# thick.net
KiCad netlist of a schematic drawn in EAGLE
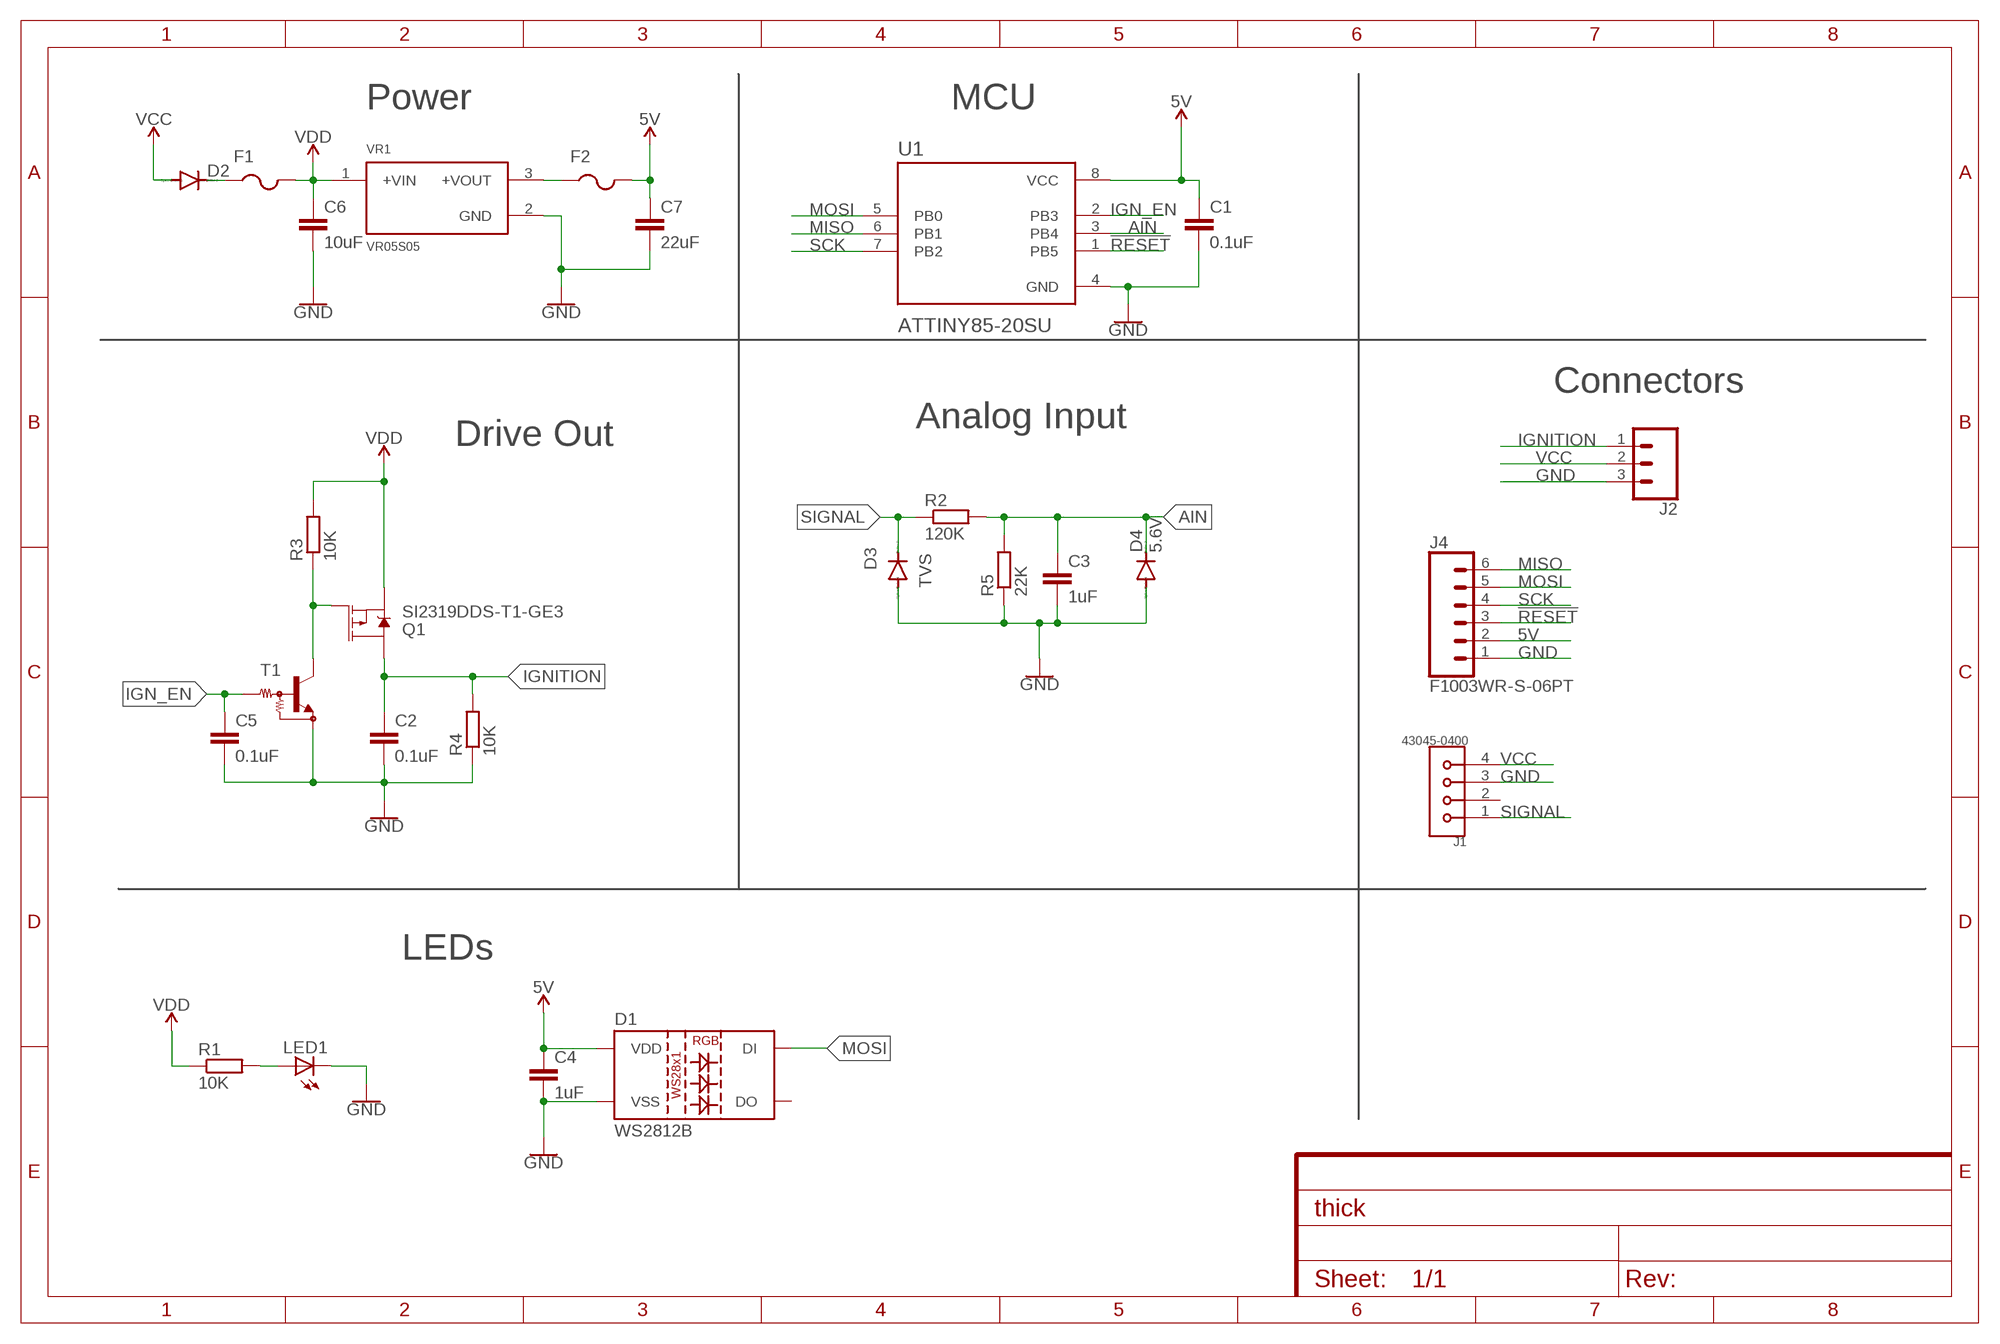
[diagram p0: schematic, sheet 1]

(export (version "E")
  (design (tool "Eeschema 10.0.6"))
  (components
    (comp (ref "C1")
      (value "0.1uF")
      (footprint "eagle-import:C0603")
      (libsource (lib "eagle-import") (part "C-EUC0603"))
    )
    (comp (ref "C2")
      (value "0.1uF")
      (footprint "eagle-import:C0603")
      (libsource (lib "eagle-import") (part "C-EUC0603"))
    )
    (comp (ref "C3")
      (value "1uF")
      (footprint "eagle-import:C0603")
      (libsource (lib "eagle-import") (part "C-EUC0603"))
    )
    (comp (ref "C4")
      (value "1uF")
      (footprint "eagle-import:C0603")
      (libsource (lib "eagle-import") (part "C-EUC0603"))
    )
    (comp (ref "C5")
      (value "0.1uF")
      (footprint "eagle-import:C0603")
      (libsource (lib "eagle-import") (part "C-EUC0603"))
    )
    (comp (ref "C6")
      (value "10uF")
      (footprint "eagle-import:C1206")
      (libsource (lib "eagle-import") (part "C-EUC1206"))
    )
    (comp (ref "C7")
      (value "22uF")
      (footprint "eagle-import:C0603")
      (libsource (lib "eagle-import") (part "C-EUC0603"))
    )
    (comp (ref "D1")
      (value "WS2812B")
      (footprint "eagle-import:WS2812B")
      (libsource (lib "eagle-import") (part "WS2812B"))
    )
    (comp (ref "D2")
      (value "DIODE-MINIMELF")
      (footprint "eagle-import:MINIMELF")
      (libsource (lib "eagle-import") (part "DIODE-MINIMELF"))
    )
    (comp (ref "D3")
      (value "TVS")
      (footprint "eagle-import:DO214AC")
      (libsource (lib "eagle-import") (part "DIODE-DO214AC"))
    )
    (comp (ref "D4")
      (value "5.6V")
      (footprint "eagle-import:MINIMELF")
      (libsource (lib "eagle-import") (part "DIODE-MINIMELF"))
    )
    (comp (ref "F1")
      (value "PTCFUSE-1206")
      (footprint "eagle-import:R1206")
      (libsource (lib "eagle-import") (part "PTCFUSE-1206"))
    )
    (comp (ref "F2")
      (value "PTCFUSE-1206")
      (footprint "eagle-import:R1206")
      (libsource (lib "eagle-import") (part "PTCFUSE-1206"))
    )
    (comp (ref "J1")
      (value "43045-0400")
      (footprint "eagle-import:MOLEX_43045-0400")
      (fields (field (name "MF") "Molex"))
      (libsource (lib "eagle-import") (part "43045-0400"))
    )
    (comp (ref "J2")
      (value "CONN_03LONGPADS")
      (footprint "eagle-import:1X03_LONGPADS")
      (libsource (lib "eagle-import") (part "CONN_03LONGPADS"))
    )
    (comp (ref "J4")
      (value "F1003WR-S-06PT")
      (footprint "eagle-import:1X06-1MM")
      (libsource (lib "eagle-import") (part "F1003WR-S-06PT"))
    )
    (comp (ref "LED1")
      (value "LEDCHIPLED_0805")
      (footprint "eagle-import:CHIPLED_0805")
      (libsource (lib "eagle-import") (part "LEDCHIPLED_0805"))
    )
    (comp (ref "Q1")
      (value "SI2319DDS-T1-GE3")
      (footprint "eagle-import:SOT23-3")
      (libsource (lib "eagle-import") (part "MOSFET_PCH-DMG2307L"))
    )
    (comp (ref "R1")
      (value "10K")
      (footprint "eagle-import:R0603")
      (libsource (lib "eagle-import") (part "R-EU_R0603"))
    )
    (comp (ref "R2")
      (value "120K")
      (footprint "eagle-import:R0603")
      (libsource (lib "eagle-import") (part "R-EU_R0603"))
    )
    (comp (ref "R3")
      (value "10K")
      (footprint "eagle-import:R0603")
      (libsource (lib "eagle-import") (part "R-EU_R0603"))
    )
    (comp (ref "R4")
      (value "10K")
      (footprint "eagle-import:R0603")
      (libsource (lib "eagle-import") (part "R-EU_R0603"))
    )
    (comp (ref "R5")
      (value "22K")
      (footprint "eagle-import:R0603")
      (libsource (lib "eagle-import") (part "R-EU_R0603"))
    )
    (comp (ref "T1")
      (value "MUN2213T1-NPN_DRIVER-SC59-BEC")
      (footprint "eagle-import:SC59-BEC")
      (libsource (lib "eagle-import") (part "-NPN_DRIVER-SC59-BECMUN2213T1"))
    )
    (comp (ref "U1")
      (value "ATTINY85-20SU")
      (footprint "eagle-import:SOIC127P798X216-8N")
      (fields (field (name "MF") "Microchip Technology"))
      (libsource (lib "eagle-import") (part "ATTINY85-20SU"))
    )
    (comp (ref "VR1")
      (value "VR05S05")
      (footprint "eagle-import:CONV_TSR_1-24150")
      (fields (field (name "MF") "Traco Power") (field (name "MP") "TSR 1-24150"))
      (libsource (lib "eagle-import") (part "TSR_1-24150"))
    )
  )
  (nets
    (net (code "1") (name "/MISO") (class "Default")
      (node (ref "J4") (pin "6") (pinfunction "6_6") (pintype "passive"))
      (node (ref "U1") (pin "6") (pinfunction "PB1_6") (pintype "bidirectional"))
    )
    (net (code "2") (name "/SCK") (class "Default")
      (node (ref "J4") (pin "4") (pinfunction "4_4") (pintype "passive"))
      (node (ref "U1") (pin "7") (pinfunction "PB2_7") (pintype "bidirectional"))
    )
    (net (code "3") (name "/~{RESET}") (class "Default")
      (node (ref "J4") (pin "3") (pinfunction "3_3") (pintype "passive"))
      (node (ref "U1") (pin "1") (pinfunction "PB5_1") (pintype "bidirectional"))
    )
    (net (code "4") (name "5V") (class "Default")
      (node (ref "C1") (pin "1") (pinfunction "1_1") (pintype "passive"))
      (node (ref "C4") (pin "1") (pinfunction "1_1") (pintype "passive"))
      (node (ref "C7") (pin "1") (pinfunction "1_1") (pintype "passive"))
      (node (ref "D1") (pin "1") (pinfunction "VDD_1") (pintype "bidirectional"))
      (node (ref "F2") (pin "2") (pinfunction "2_2") (pintype "passive"))
      (node (ref "J4") (pin "2") (pinfunction "2_2") (pintype "passive"))
      (node (ref "U1") (pin "8") (pinfunction "VCC_8") (pintype "power_in"))
    )
    (net (code "5") (name "AIN") (class "Default")
      (node (ref "C3") (pin "1") (pinfunction "1_1") (pintype "passive"))
      (node (ref "D4") (pin "C") (pinfunction "C_C") (pintype "passive"))
      (node (ref "R2") (pin "2") (pinfunction "2_2") (pintype "passive"))
      (node (ref "R5") (pin "2") (pinfunction "2_2") (pintype "passive"))
      (node (ref "U1") (pin "3") (pinfunction "PB4_3") (pintype "bidirectional"))
    )
    (net (code "6") (name "GND") (class "Default")
      (node (ref "C1") (pin "2") (pinfunction "2_2") (pintype "passive"))
      (node (ref "C2") (pin "2") (pinfunction "2_2") (pintype "passive"))
      (node (ref "C3") (pin "2") (pinfunction "2_2") (pintype "passive"))
      (node (ref "C4") (pin "2") (pinfunction "2_2") (pintype "passive"))
      (node (ref "C5") (pin "2") (pinfunction "2_2") (pintype "passive"))
      (node (ref "C6") (pin "2") (pinfunction "2_2") (pintype "passive"))
      (node (ref "C7") (pin "2") (pinfunction "2_2") (pintype "passive"))
      (node (ref "D1") (pin "3") (pinfunction "VSS_3") (pintype "bidirectional"))
      (node (ref "D3") (pin "A") (pinfunction "A_A") (pintype "passive"))
      (node (ref "D4") (pin "A") (pinfunction "A_A") (pintype "passive"))
      (node (ref "J1") (pin "3") (pinfunction "3_3") (pintype "passive"))
      (node (ref "J2") (pin "3") (pinfunction "3_3") (pintype "passive"))
      (node (ref "J4") (pin "1") (pinfunction "1_1") (pintype "passive"))
      (node (ref "LED1") (pin "C") (pinfunction "C_C") (pintype "passive"))
      (node (ref "R4") (pin "1") (pinfunction "1_1") (pintype "passive"))
      (node (ref "R5") (pin "1") (pinfunction "1_1") (pintype "passive"))
      (node (ref "T1") (pin "E") (pinfunction "E_E") (pintype "passive"))
      (node (ref "U1") (pin "4") (pinfunction "GND_4") (pintype "power_in"))
      (node (ref "VR1") (pin "2") (pinfunction "GND_2") (pintype "power_in"))
    )
    (net (code "7") (name "IGNITION") (class "Default")
      (node (ref "C2") (pin "1") (pinfunction "1_1") (pintype "passive"))
      (node (ref "J2") (pin "1") (pinfunction "1_1") (pintype "passive"))
      (node (ref "Q1") (pin "3") (pinfunction "D_3") (pintype "bidirectional"))
      (node (ref "R4") (pin "2") (pinfunction "2_2") (pintype "passive"))
    )
    (net (code "8") (name "IGN_EN") (class "Default")
      (node (ref "C5") (pin "1") (pinfunction "1_1") (pintype "passive"))
      (node (ref "T1") (pin "B") (pinfunction "B_B") (pintype "passive"))
      (node (ref "U1") (pin "2") (pinfunction "PB3_2") (pintype "bidirectional"))
    )
    (net (code "9") (name "MOSI") (class "Default")
      (node (ref "D1") (pin "4") (pinfunction "DI_4") (pintype "bidirectional"))
      (node (ref "J4") (pin "5") (pinfunction "5_5") (pintype "passive"))
      (node (ref "U1") (pin "5") (pinfunction "PB0_5") (pintype "bidirectional"))
    )
    (net (code "10") (name "Net-(D2-PadC)") (class "Default")
      (node (ref "D2") (pin "C") (pinfunction "C_C") (pintype "passive"))
      (node (ref "F1") (pin "1") (pinfunction "1_1") (pintype "passive"))
    )
    (net (code "11") (name "Net-(LED1-PadA)") (class "Default")
      (node (ref "LED1") (pin "A") (pinfunction "A_A") (pintype "passive"))
      (node (ref "R1") (pin "2") (pinfunction "2_2") (pintype "passive"))
    )
    (net (code "12") (name "Net-(Q1-G)") (class "Default")
      (node (ref "Q1") (pin "1") (pinfunction "G_1") (pintype "bidirectional"))
      (node (ref "R3") (pin "1") (pinfunction "1_1") (pintype "passive"))
      (node (ref "T1") (pin "C") (pinfunction "C_C") (pintype "passive"))
    )
    (net (code "13") (name "Net-(VR1-+VOUT)") (class "Default")
      (node (ref "F2") (pin "1") (pinfunction "1_1") (pintype "passive"))
      (node (ref "VR1") (pin "3") (pinfunction "+VOUT_3") (pintype "output"))
    )
    (net (code "14") (name "SIGNAL") (class "Default")
      (node (ref "D3") (pin "C") (pinfunction "C_C") (pintype "passive"))
      (node (ref "J1") (pin "1") (pinfunction "1_1") (pintype "passive"))
      (node (ref "R2") (pin "1") (pinfunction "1_1") (pintype "passive"))
    )
    (net (code "15") (name "VCC") (class "Default")
      (node (ref "D2") (pin "A") (pinfunction "A_A") (pintype "passive"))
      (node (ref "J1") (pin "4") (pinfunction "4_4") (pintype "passive"))
      (node (ref "J2") (pin "2") (pinfunction "2_2") (pintype "passive"))
    )
    (net (code "16") (name "VDD") (class "Default")
      (node (ref "C6") (pin "1") (pinfunction "1_1") (pintype "passive"))
      (node (ref "F1") (pin "2") (pinfunction "2_2") (pintype "passive"))
      (node (ref "Q1") (pin "2") (pinfunction "S_2") (pintype "bidirectional"))
      (node (ref "R1") (pin "1") (pinfunction "1_1") (pintype "passive"))
      (node (ref "R3") (pin "2") (pinfunction "2_2") (pintype "passive"))
      (node (ref "VR1") (pin "1") (pinfunction "+VIN_1") (pintype "input"))
    )
    (net (code "17") (name "unconnected-(D1-DO-Pad2)") (class "Default")
      (node (ref "D1") (pin "2") (pinfunction "DO_2") (pintype "bidirectional"))
    )
    (net (code "18") (name "unconnected-(J1-Pad2)") (class "Default")
      (node (ref "J1") (pin "2") (pinfunction "2_2") (pintype "passive"))
    )
  )
)
